# sma_antenna.net
KiCad netlist of a schematic drawn in EAGLE
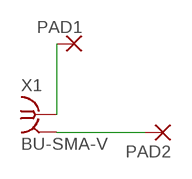
[diagram p0: schematic, sheet 1]

(export (version "E")
  (design (tool "Eeschema 10.0.6"))
  (components
    (comp (ref "PAD1")
      (value "3,81/1,4")
      (footprint "eagle-import:3,81_1,4")
      (libsource (lib "eagle-import") (part "3,81/1,4"))
    )
    (comp (ref "PAD2")
      (value "3,81/1,4")
      (footprint "eagle-import:3,81_1,4")
      (libsource (lib "eagle-import") (part "3,81/1,4"))
    )
    (comp (ref "X1")
      (value "BU-SMA-V")
      (footprint "eagle-import:BU-SMA-V")
      (libsource (lib "eagle-import") (part "BU-SMA-V"))
    )
  )
  (nets
    (net (code "1") (name "Net-(PAD1-P)") (class "Default")
      (node (ref "PAD1") (pin "1") (pinfunction "P_1") (pintype "passive"))
      (node (ref "X1") (pin "1") (pinfunction "1_1") (pintype "passive"))
    )
    (net (code "2") (name "Net-(PAD2-P)") (class "Default")
      (node (ref "PAD2") (pin "1") (pinfunction "P_1") (pintype "passive"))
      (node (ref "X1") (pin "2") (pinfunction "2_2") (pintype "passive"))
      (node (ref "X1") (pin "3") (pinfunction "2_3") (pintype "passive"))
      (node (ref "X1") (pin "4") (pinfunction "2_4") (pintype "passive"))
      (node (ref "X1") (pin "5") (pinfunction "2_5") (pintype "passive"))
    )
  )
)
